# Display.net
KiCad netlist of a schematic drawn in Altium Designer
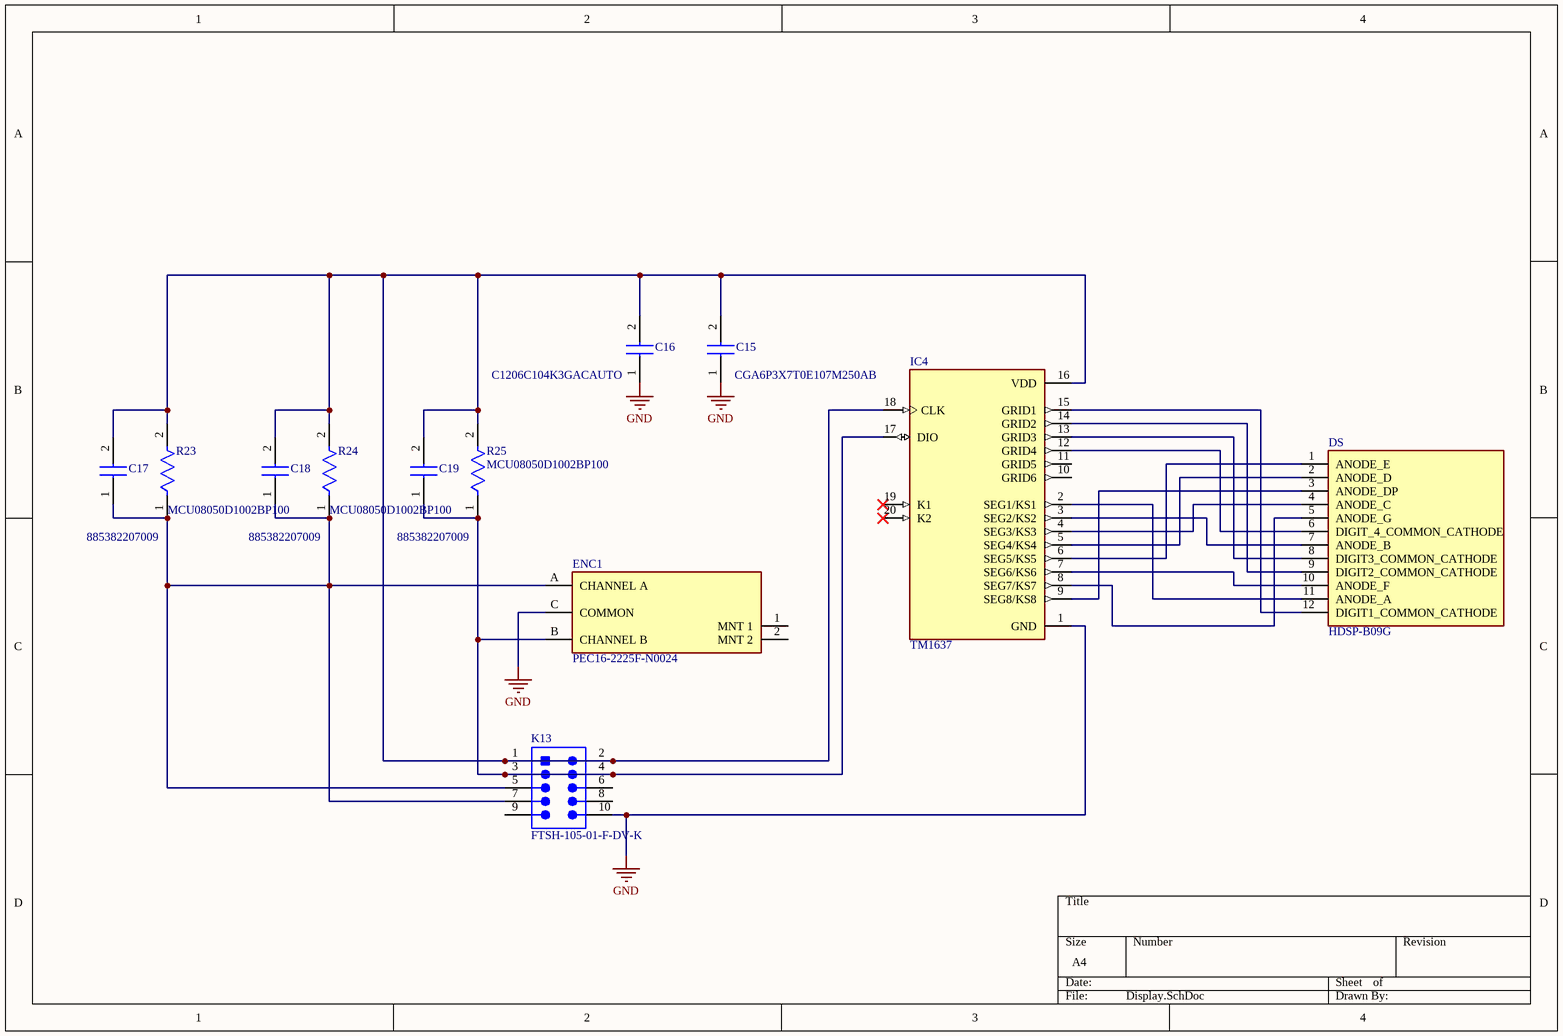
[diagram p0: Display.SchDoc]

(export (version "E")
  (design (tool "Eeschema 10.0.6"))
  (components
    (comp (ref "C15")
      (value "CGA6P3X7T0E107M250AB")
      (footprint "SamacSys:CAPC3225X280N")
      (description "Capacitor")
      (libsource (lib "*") (part "CGA6P3X7T0E107M250AB"))
    )
    (comp (ref "C16")
      (value "C1206C104K3GACAUTO")
      (footprint "SamacSys:CAPC3216X180N")
      (description "Capacitor")
      (libsource (lib "*") (part "C1206C104K3GACAUTO"))
    )
    (comp (ref "C17")
      (value "885382207009")
      (footprint "SamacSys:CAPC2012X135N")
      (description "Capacitor")
      (libsource (lib "*") (part "885382207009"))
    )
    (comp (ref "C18")
      (value "885382207009")
      (footprint "SamacSys:CAPC2012X135N")
      (description "Capacitor")
      (libsource (lib "*") (part "885382207009"))
    )
    (comp (ref "C19")
      (value "885382207009")
      (footprint "SamacSys:CAPC2012X135N")
      (description "Capacitor")
      (libsource (lib "*") (part "885382207009"))
    )
    (comp (ref "DS")
      (value "HDSP-B09G")
      (footprint "AVAGO_HDSP-B09G")
      (fields (field (name "MF") "Broadcom Limited"))
      (libsource (lib "HDSP-B09G") (part "HDSP-B09G"))
    )
    (comp (ref "ENC1")
      (value "PEC16-2225F-N0024")
      (footprint "FP-PEC16-2225F-N0024-MFG")
      (description "ROTARY ENCODER MECHANICAL 24PPR")
      (libsource (lib "Altium Content Vault") (part "29c470f7ccee8b15657efb0c94ebc83"))
    )
    (comp (ref "IC4")
      (value "TM1637")
      (footprint "DIP778W43P254L2612H431Q20N")
      (description "LED Drive Control Special Circuit")
      (fields (field (name "MF") "Titan Micro Electronics"))
      (libsource (lib "TM1637") (part "TM1637"))
    )
    (comp (ref "K13")
      (value "FTSH-105-01-F-DV-K")
      (footprint "SMTC-FTSH-105-01-L-DV-K_V")
      (description "Male Header, Pitch 1.27 mm, 2 x 5 Position, Height 6.12 mm, RoHS, Tube")
      (fields (field (name "MANUFACTURER") "Samtec"))
      (libsource (lib "Altium Content Vault") (part "CN-2P-M-R10"))
    )
    (comp (ref "R23")
      (value "MCU08050D1002BP100")
      (footprint "FP-MCU0805-IPC_C")
      (description "RES 1.05K OHM 0.5% 1/5W 0805")
      (fields (field (name "TOLERANCE") "0.1%"))
      (libsource (lib "Altium Content Vault") (part "1029c3af85768c4190bb7ad29bc67b5"))
    )
    (comp (ref "R24")
      (value "MCU08050D1002BP100")
      (footprint "FP-MCU0805-IPC_C")
      (description "RES 1.05K OHM 0.5% 1/5W 0805")
      (fields (field (name "TOLERANCE") "0.1%"))
      (libsource (lib "Altium Content Vault") (part "1029c3af85768c4190bb7ad29bc67b5"))
    )
    (comp (ref "R25")
      (value "MCU08050D1002BP100")
      (footprint "FP-MCU0805-IPC_C")
      (description "RES 1.05K OHM 0.5% 1/5W 0805")
      (fields (field (name "TOLERANCE") "0.1%"))
      (libsource (lib "Altium Content Vault") (part "1029c3af85768c4190bb7ad29bc67b5"))
    )
  )
  (nets
    (net (code "1") (name "GND") (class "Default")
      (node (ref "C15") (pin "1") (pinfunction "1_1") (pintype "passive"))
      (node (ref "C16") (pin "1") (pinfunction "1_1") (pintype "passive"))
      (node (ref "ENC1") (pin "C") (pinfunction "COMMON_C") (pintype "passive"))
      (node (ref "IC4") (pin "1") (pinfunction "GND_1") (pintype "power_in"))
      (node (ref "K13") (pin "10") (pinfunction "10_10") (pintype "passive"))
    )
    (net (code "2") (name "Net-(DS-ANODE_A)") (class "Default")
      (node (ref "DS") (pin "11") (pinfunction "ANODE_A_11") (pintype "passive"))
      (node (ref "IC4") (pin "2") (pinfunction "SEG1/KS1_2") (pintype "output"))
    )
    (net (code "3") (name "Net-(DS-ANODE_B)") (class "Default")
      (node (ref "DS") (pin "7") (pinfunction "ANODE_B_7") (pintype "passive"))
      (node (ref "IC4") (pin "3") (pinfunction "SEG2/KS2_3") (pintype "output"))
    )
    (net (code "4") (name "Net-(DS-ANODE_C)") (class "Default")
      (node (ref "DS") (pin "4") (pinfunction "ANODE_C_4") (pintype "passive"))
      (node (ref "IC4") (pin "4") (pinfunction "SEG3/KS3_4") (pintype "output"))
    )
    (net (code "5") (name "Net-(DS-ANODE_D)") (class "Default")
      (node (ref "DS") (pin "2") (pinfunction "ANODE_D_2") (pintype "passive"))
      (node (ref "IC4") (pin "5") (pinfunction "SEG4/KS4_5") (pintype "output"))
    )
    (net (code "6") (name "Net-(DS-ANODE_DP)") (class "Default")
      (node (ref "DS") (pin "3") (pinfunction "ANODE_DP_3") (pintype "passive"))
      (node (ref "IC4") (pin "9") (pinfunction "SEG8/KS8_9") (pintype "output"))
    )
    (net (code "7") (name "Net-(DS-ANODE_E)") (class "Default")
      (node (ref "DS") (pin "1") (pinfunction "ANODE_E_1") (pintype "passive"))
      (node (ref "IC4") (pin "6") (pinfunction "SEG5/KS5_6") (pintype "output"))
    )
    (net (code "8") (name "Net-(DS-ANODE_F)") (class "Default")
      (node (ref "DS") (pin "10") (pinfunction "ANODE_F_10") (pintype "passive"))
      (node (ref "IC4") (pin "7") (pinfunction "SEG6/KS6_7") (pintype "output"))
    )
    (net (code "9") (name "Net-(DS-ANODE_G)") (class "Default")
      (node (ref "DS") (pin "5") (pinfunction "ANODE_G_5") (pintype "passive"))
      (node (ref "IC4") (pin "8") (pinfunction "SEG7/KS7_8") (pintype "output"))
    )
    (net (code "10") (name "Net-(DS-DIGIT1_COMMON_CATHODE)") (class "Default")
      (node (ref "DS") (pin "12") (pinfunction "DIGIT1_COMMON_CATHODE_12") (pintype "passive"))
      (node (ref "IC4") (pin "15") (pinfunction "GRID1_15") (pintype "output"))
    )
    (net (code "11") (name "Net-(DS-DIGIT2_COMMON_CATHODE)") (class "Default")
      (node (ref "DS") (pin "9") (pinfunction "DIGIT2_COMMON_CATHODE_9") (pintype "passive"))
      (node (ref "IC4") (pin "14") (pinfunction "GRID2_14") (pintype "output"))
    )
    (net (code "12") (name "Net-(DS-DIGIT3_COMMON_CATHODE)") (class "Default")
      (node (ref "DS") (pin "8") (pinfunction "DIGIT3_COMMON_CATHODE_8") (pintype "passive"))
      (node (ref "IC4") (pin "13") (pinfunction "GRID3_13") (pintype "output"))
    )
    (net (code "13") (name "Net-(DS-DIGIT_4_COMMON_CATHODE)") (class "Default")
      (node (ref "DS") (pin "6") (pinfunction "DIGIT_4_COMMON_CATHODE_6") (pintype "passive"))
      (node (ref "IC4") (pin "12") (pinfunction "GRID4_12") (pintype "output"))
    )
    (net (code "14") (name "Net-(ENC1-CHANNEL_A)") (class "Default")
      (node (ref "C17") (pin "1") (pinfunction "1_1") (pintype "passive"))
      (node (ref "C18") (pin "1") (pinfunction "1_1") (pintype "passive"))
      (node (ref "ENC1") (pin "A") (pinfunction "CHANNEL_A_A") (pintype "passive"))
      (node (ref "K13") (pin "5") (pinfunction "5_5") (pintype "passive"))
      (node (ref "K13") (pin "7") (pinfunction "7_7") (pintype "passive"))
      (node (ref "R23") (pin "1") (pinfunction "1_1") (pintype "passive"))
      (node (ref "R24") (pin "1") (pinfunction "1_1") (pintype "passive"))
    )
    (net (code "15") (name "Net-(ENC1-CHANNEL_B)") (class "Default")
      (node (ref "C19") (pin "1") (pinfunction "1_1") (pintype "passive"))
      (node (ref "ENC1") (pin "B") (pinfunction "CHANNEL_B_B") (pintype "passive"))
      (node (ref "IC4") (pin "17") (pinfunction "DIO_17") (pintype "bidirectional"))
      (node (ref "K13") (pin "3") (pinfunction "3_3") (pintype "passive"))
      (node (ref "K13") (pin "4") (pinfunction "4_4") (pintype "passive"))
      (node (ref "R25") (pin "1") (pinfunction "1_1") (pintype "passive"))
    )
    (net (code "16") (name "Net-(IC4-CLK)") (class "Default")
      (node (ref "C15") (pin "2") (pinfunction "2_2") (pintype "passive"))
      (node (ref "C16") (pin "2") (pinfunction "2_2") (pintype "passive"))
      (node (ref "C17") (pin "2") (pinfunction "2_2") (pintype "passive"))
      (node (ref "C18") (pin "2") (pinfunction "2_2") (pintype "passive"))
      (node (ref "C19") (pin "2") (pinfunction "2_2") (pintype "passive"))
      (node (ref "IC4") (pin "16") (pinfunction "VDD_16") (pintype "power_in"))
      (node (ref "IC4") (pin "18") (pinfunction "CLK_18") (pintype "input"))
      (node (ref "K13") (pin "1") (pinfunction "1_1") (pintype "passive"))
      (node (ref "K13") (pin "2") (pinfunction "2_2") (pintype "passive"))
      (node (ref "R23") (pin "2") (pinfunction "2_2") (pintype "passive"))
      (node (ref "R24") (pin "2") (pinfunction "2_2") (pintype "passive"))
      (node (ref "R25") (pin "2") (pinfunction "2_2") (pintype "passive"))
    )
    (net (code "17") (name "unconnected-(ENC1-MNT_1-Pad1)") (class "Default")
      (node (ref "ENC1") (pin "1") (pinfunction "MNT_1_1") (pintype "passive"))
    )
    (net (code "18") (name "unconnected-(ENC1-MNT_2-Pad2)") (class "Default")
      (node (ref "ENC1") (pin "2") (pinfunction "MNT_2_2") (pintype "passive"))
    )
    (net (code "19") (name "unconnected-(IC4-GRID5-Pad11)") (class "Default")
      (node (ref "IC4") (pin "11") (pinfunction "GRID5_11") (pintype "output"))
    )
    (net (code "20") (name "unconnected-(IC4-GRID6-Pad10)") (class "Default")
      (node (ref "IC4") (pin "10") (pinfunction "GRID6_10") (pintype "output"))
    )
    (net (code "21") (name "unconnected-(IC4-K1-Pad19)") (class "Default")
      (node (ref "IC4") (pin "19") (pinfunction "K1_19") (pintype "input+no_connect"))
    )
    (net (code "22") (name "unconnected-(IC4-K2-Pad20)") (class "Default")
      (node (ref "IC4") (pin "20") (pinfunction "K2_20") (pintype "input+no_connect"))
    )
    (net (code "23") (name "unconnected-(K13-Pad6)") (class "Default")
      (node (ref "K13") (pin "6") (pinfunction "6_6") (pintype "passive"))
    )
    (net (code "24") (name "unconnected-(K13-Pad8)") (class "Default")
      (node (ref "K13") (pin "8") (pinfunction "8_8") (pintype "passive"))
    )
    (net (code "25") (name "unconnected-(K13-Pad9)") (class "Default")
      (node (ref "K13") (pin "9") (pinfunction "9_9") (pintype "passive"))
    )
  )
)
